# LPCB219_-_OVERVIEW.net
KiCad netlist of a schematic drawn in Altium Designer
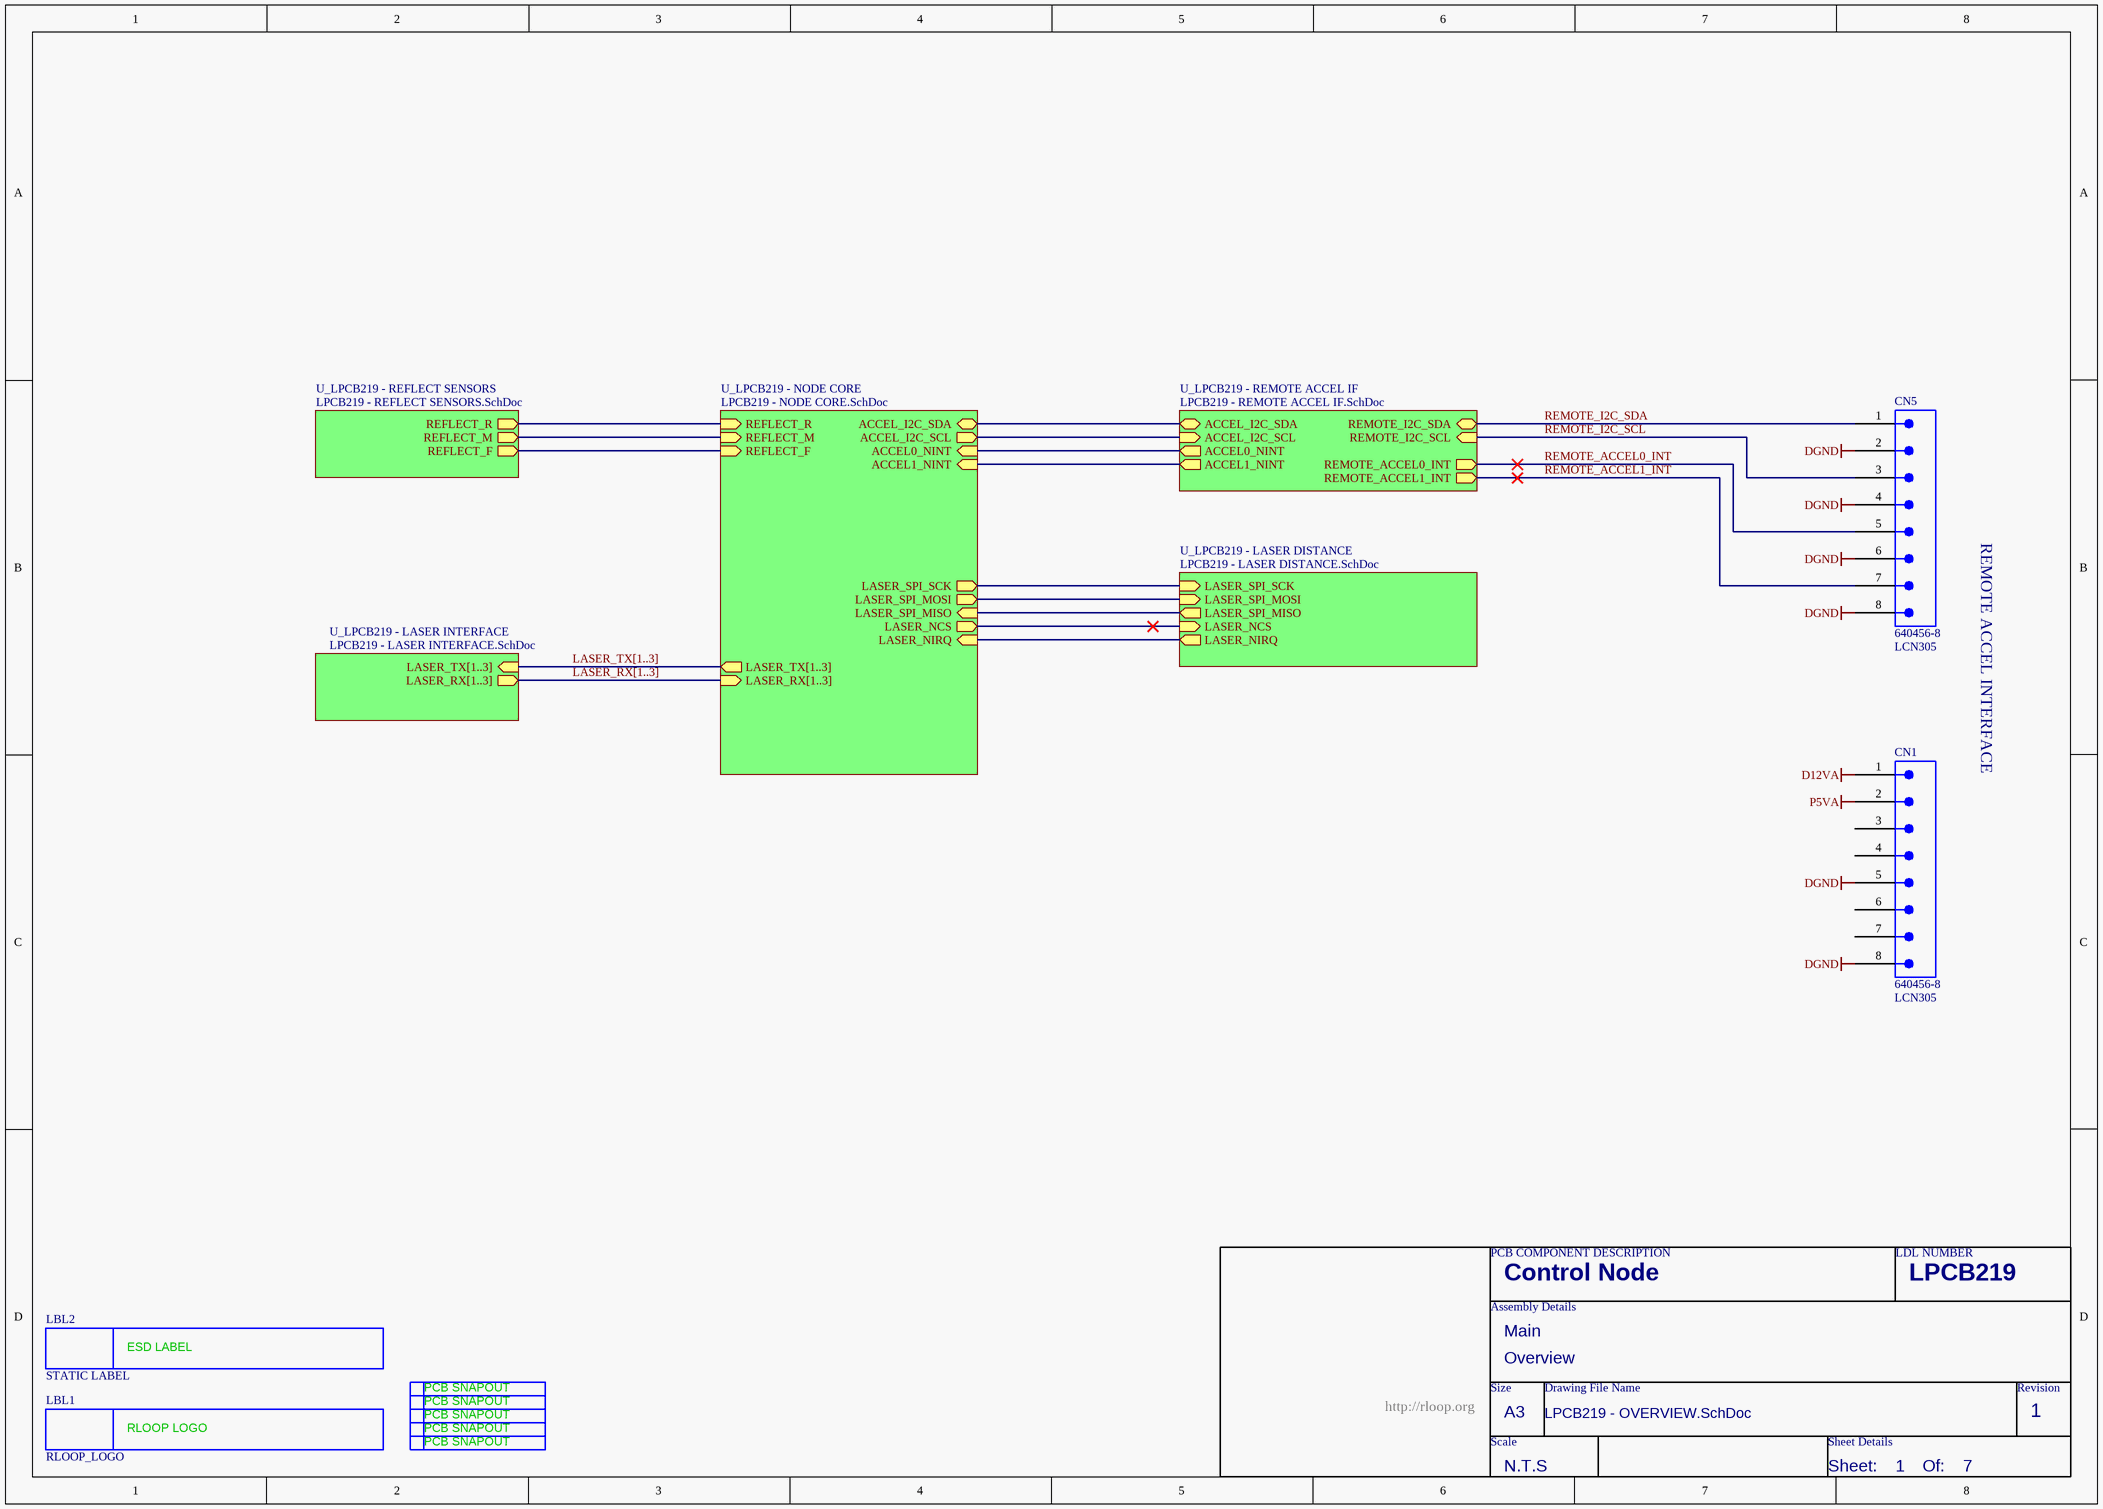
[diagram p0: LPCB219 - OVERVIEW.SchDoc]

(export (version "E")
  (design (tool "Eeschema 10.0.6"))
  (components
    (comp (ref "CN1")
      (value "640456-8")
      (footprint "640456-8")
      (description "Connector, Male Header, 8 Way")
      (fields (field (name "LDL_NUMBER") "LCN305"))
      (libsource (lib "LDL_Connectors") (part "640456-8"))
    )
    (comp (ref "CN5")
      (value "640456-8")
      (footprint "640456-8")
      (description "Connector, Male Header, 8 Way")
      (fields (field (name "LDL_NUMBER") "LCN305"))
      (libsource (lib "LDL_Connectors") (part "640456-8"))
    )
    (comp (ref "LBL1")
      (value "RLOOP_LOGO")
      (footprint "RLOOP_LOGO")
      (libsource (lib "LDL_Mechanical") (part "RLOOP_LOGO"))
    )
    (comp (ref "LBL2")
      (value "STATIC LABEL")
      (footprint "STATIC_LABEL")
      (libsource (lib "LDL_Mechanical") (part "STATIC LABEL"))
    )
    (comp (ref "SN2")
      (value "PCB_SNAPOUT")
      (footprint "SNAPOUT_NEW")
      (libsource (lib "LDL_Mechanical") (part "PCB_SNAPOUT"))
    )
    (comp (ref "SN3")
      (value "PCB_SNAPOUT")
      (footprint "SNAPOUT_NEW")
      (libsource (lib "LDL_Mechanical") (part "PCB_SNAPOUT"))
    )
    (comp (ref "SN4")
      (value "PCB_SNAPOUT")
      (footprint "SNAPOUT_NEW")
      (libsource (lib "LDL_Mechanical") (part "PCB_SNAPOUT"))
    )
    (comp (ref "SN5")
      (value "PCB_SNAPOUT")
      (footprint "SNAPOUT_NEW")
      (libsource (lib "LDL_Mechanical") (part "PCB_SNAPOUT"))
    )
    (comp (ref "SN6")
      (value "PCB_SNAPOUT")
      (footprint "SNAPOUT_NEW")
      (libsource (lib "LDL_Mechanical") (part "PCB_SNAPOUT"))
    )
  )
  (nets
    (net (code "21") (name "/REMOTE_ACCEL0_INT") (class "Default")
      (node (ref "CN5") (pin "5") (pinfunction "5_5") (pintype "passive"))
    )
    (net (code "22") (name "/REMOTE_ACCEL1_INT") (class "Default")
      (node (ref "CN5") (pin "7") (pinfunction "7_7") (pintype "passive"))
    )
    (net (code "23") (name "/REMOTE_I2C_SCL") (class "Default")
      (node (ref "CN5") (pin "3") (pinfunction "3_3") (pintype "passive"))
    )
    (net (code "24") (name "/REMOTE_I2C_SDA") (class "Default")
      (node (ref "CN5") (pin "1") (pinfunction "1_1") (pintype "passive"))
    )
    (net (code "25") (name "D12VA") (class "Default")
      (node (ref "CN1") (pin "1") (pinfunction "1_1") (pintype "passive"))
    )
    (net (code "26") (name "DGND") (class "Default")
      (node (ref "CN1") (pin "5") (pinfunction "5_5") (pintype "passive"))
      (node (ref "CN1") (pin "8") (pinfunction "8_8") (pintype "passive"))
      (node (ref "CN5") (pin "2") (pinfunction "2_2") (pintype "passive"))
      (node (ref "CN5") (pin "4") (pinfunction "4_4") (pintype "passive"))
      (node (ref "CN5") (pin "6") (pinfunction "6_6") (pintype "passive"))
      (node (ref "CN5") (pin "8") (pinfunction "8_8") (pintype "passive"))
    )
    (net (code "27") (name "P5VA") (class "Default")
      (node (ref "CN1") (pin "2") (pinfunction "2_2") (pintype "passive"))
    )
    (net (code "28") (name "unconnected-(CN1-Pad3)") (class "Default")
      (node (ref "CN1") (pin "3") (pinfunction "3_3") (pintype "passive"))
    )
    (net (code "29") (name "unconnected-(CN1-Pad4)") (class "Default")
      (node (ref "CN1") (pin "4") (pinfunction "4_4") (pintype "passive"))
    )
    (net (code "30") (name "unconnected-(CN1-Pad6)") (class "Default")
      (node (ref "CN1") (pin "6") (pinfunction "6_6") (pintype "passive"))
    )
    (net (code "31") (name "unconnected-(CN1-Pad7)") (class "Default")
      (node (ref "CN1") (pin "7") (pinfunction "7_7") (pintype "passive"))
    )
  )
)
